# 2-Amplifier.net
KiCad netlist of a schematic drawn in Altium Designer
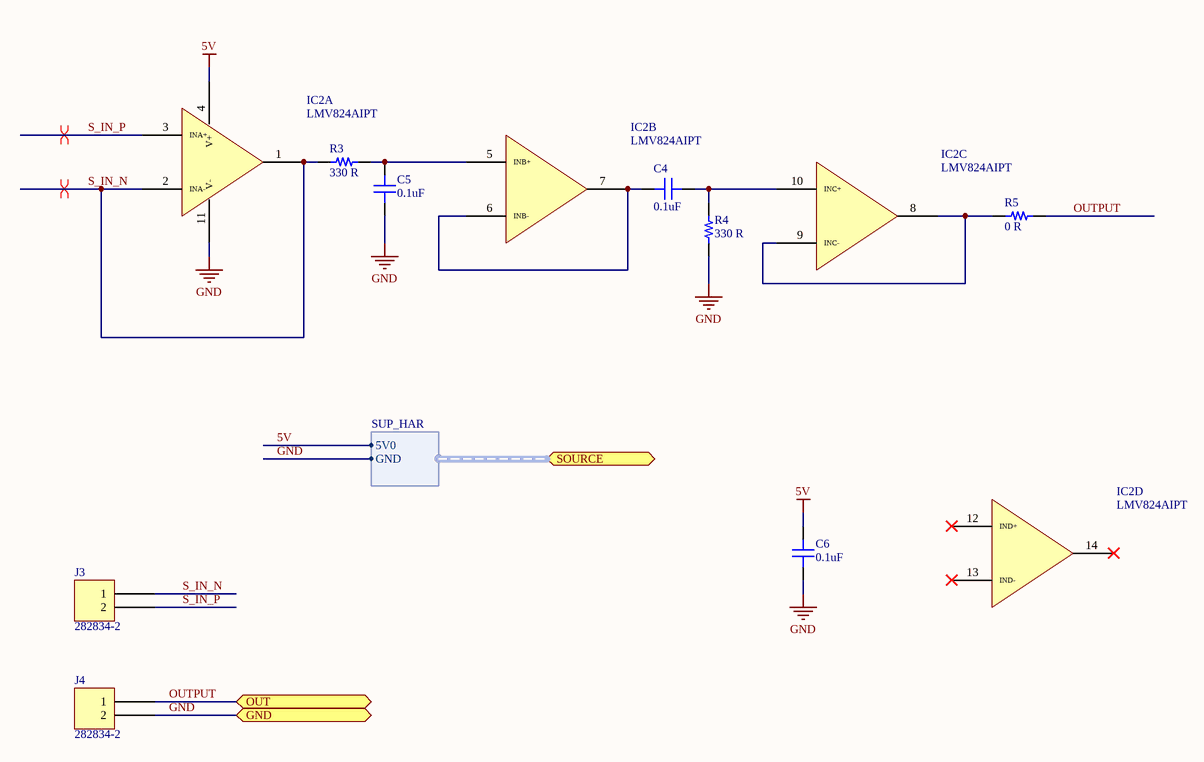
[diagram p0: 2-Amplifier.SchDoc]

(export (version "E")
  (design (tool "Eeschema 10.0.6"))
  (components
    (comp (ref "C4")
      (value "0.1uF")
      (footprint "CAP 0805_2012")
      (description "CAP CER 5.6PF 500V C0G/NP0 0805")
      (fields (field (name "PART NUMBER") "CBR08C569BCGAC") (field (name "MANUFACTURER") "KEMET"))
      (libsource (lib "Celestial Altium Library - altium_library") (part "Capacitor"))
    )
    (comp (ref "C5")
      (value "0.1uF")
      (footprint "CAP 0805_2012")
      (description "CAP CER 5.6PF 500V C0G/NP0 0805")
      (fields (field (name "PART NUMBER") "CBR08C569BCGAC") (field (name "MANUFACTURER") "KEMET"))
      (libsource (lib "Celestial Altium Library - altium_library") (part "Capacitor"))
    )
    (comp (ref "C6")
      (value "0.1uF")
      (footprint "CAP 0805_2012")
      (description "CAP CER 5.6PF 500V C0G/NP0 0805")
      (fields (field (name "PART NUMBER") "CBR08C569BCGAC") (field (name "MANUFACTURER") "KEMET"))
      (libsource (lib "Celestial Altium Library - altium_library") (part "Capacitor"))
    )
    (comp (ref "IC2")
      (value "LMV824AIPT")
      (footprint "TI TSSOP-14 PW")
      (description "IC OPAMP GP 4 CIRCUIT 14TSSOP")
      (fields (field (name "MANUFACTURER") "STMicroelectronics"))
      (libsource (lib "Celestial Altium Library - altium_library") (part "TI LMV82x 14 PIN"))
    )
    (comp (ref "J3")
      (value "282834-2")
      (footprint "TE 282834-2")
      (description "TERM BLK 2P SIDE ENT 2.54MM PCB")
      (fields (field (name "MANUFACTURER") "TE Connectivity AMP Connectors") (field (name "VOLTAGE") "150V"))
      (libsource (lib "Celestial Altium Library - altium_library") (part "2 Pin"))
    )
    (comp (ref "J4")
      (value "282834-2")
      (footprint "TE 282834-2")
      (description "TERM BLK 2P SIDE ENT 2.54MM PCB")
      (fields (field (name "MANUFACTURER") "TE Connectivity AMP Connectors") (field (name "VOLTAGE") "150V"))
      (libsource (lib "Celestial Altium Library - altium_library") (part "2 Pin"))
    )
    (comp (ref "R3")
      (value "330 R")
      (footprint "RES 0805_2012")
      (description "RES 82K OHM 0.5% 1/8W 0805")
      (fields
        (field (name "PART NUMBER") "RNCF0805DTE82K0")
        (field (name "MANUFACTURER") "Stackpole Electronics Inc")
      )
      (libsource (lib "Celestial Altium Library - altium_library") (part "Resistor"))
    )
    (comp (ref "R4")
      (value "330 R")
      (footprint "RES 0805_2012")
      (description "RES 82K OHM 0.5% 1/8W 0805")
      (fields
        (field (name "PART NUMBER") "RNCF0805DTE82K0")
        (field (name "MANUFACTURER") "Stackpole Electronics Inc")
      )
      (libsource (lib "Celestial Altium Library - altium_library") (part "Resistor"))
    )
    (comp (ref "R5")
      (value "0 R")
      (footprint "RES 0805_2012")
      (description "RES 82K OHM 0.5% 1/8W 0805")
      (fields
        (field (name "PART NUMBER") "RNCF0805DTE82K0")
        (field (name "MANUFACTURER") "Stackpole Electronics Inc")
      )
      (libsource (lib "Celestial Altium Library - altium_library") (part "Resistor"))
    )
  )
  (nets
    (net (code "2") (name "/OUTPUT") (class "Default")
      (node (ref "J4") (pin "1") (pinfunction "1_1") (pintype "passive"))
      (node (ref "R5") (pin "1") (pinfunction "1_1") (pintype "passive"))
    )
    (net (code "3") (name "/S_IN_N") (class "Default")
      (node (ref "IC2") (pin "1") (pinfunction "OUT_1") (pintype "passive"))
      (node (ref "IC2") (pin "2") (pinfunction "INA-_2") (pintype "passive"))
      (node (ref "J3") (pin "1") (pinfunction "1_1") (pintype "passive"))
      (node (ref "R3") (pin "1") (pinfunction "1_1") (pintype "passive"))
    )
    (net (code "4") (name "/S_IN_P") (class "Default")
      (node (ref "IC2") (pin "3") (pinfunction "INA+_3") (pintype "passive"))
      (node (ref "J3") (pin "2") (pinfunction "2_2") (pintype "passive"))
    )
    (net (code "6") (name "5V") (class "Default")
      (node (ref "C6") (pin "2") (pinfunction "2_2") (pintype "passive"))
      (node (ref "IC2") (pin "4") (pinfunction "V+_4") (pintype "power_in"))
    )
    (net (code "7") (name "GND") (class "Default")
      (node (ref "C5") (pin "1") (pinfunction "1_1") (pintype "passive"))
      (node (ref "C6") (pin "1") (pinfunction "1_1") (pintype "passive"))
      (node (ref "IC2") (pin "11") (pinfunction "V-_11") (pintype "power_in"))
      (node (ref "J4") (pin "2") (pinfunction "2_2") (pintype "passive"))
      (node (ref "R4") (pin "1") (pinfunction "1_1") (pintype "passive"))
    )
    (net (code "8") (name "Net-(IC2B-INB+)") (class "Default")
      (node (ref "C5") (pin "2") (pinfunction "2_2") (pintype "passive"))
      (node (ref "IC2") (pin "5") (pinfunction "INB+_5") (pintype "passive"))
      (node (ref "R3") (pin "2") (pinfunction "2_2") (pintype "passive"))
    )
    (net (code "9") (name "Net-(IC2B-INB-)") (class "Default")
      (node (ref "C4") (pin "2") (pinfunction "2_2") (pintype "passive"))
      (node (ref "IC2") (pin "6") (pinfunction "INB-_6") (pintype "passive"))
      (node (ref "IC2") (pin "7") (pinfunction "OUTB_7") (pintype "passive"))
    )
    (net (code "10") (name "Net-(IC2C-INC+)") (class "Default")
      (node (ref "C4") (pin "1") (pinfunction "1_1") (pintype "passive"))
      (node (ref "IC2") (pin "10") (pinfunction "INC+_10") (pintype "passive"))
      (node (ref "R4") (pin "2") (pinfunction "2_2") (pintype "passive"))
    )
    (net (code "11") (name "Net-(IC2C-INC-)") (class "Default")
      (node (ref "IC2") (pin "8") (pinfunction "OUTC_8") (pintype "passive"))
      (node (ref "IC2") (pin "9") (pinfunction "INC-_9") (pintype "passive"))
      (node (ref "R5") (pin "2") (pinfunction "2_2") (pintype "passive"))
    )
    (net (code "12") (name "unconnected-(IC2D-IND+-Pad12)") (class "Default")
      (node (ref "IC2") (pin "12") (pinfunction "IND+_12") (pintype "passive+no_connect"))
    )
    (net (code "13") (name "unconnected-(IC2D-IND--Pad13)") (class "Default")
      (node (ref "IC2") (pin "13") (pinfunction "IND-_13") (pintype "passive+no_connect"))
    )
    (net (code "14") (name "unconnected-(IC2D-OUTD-Pad14)") (class "Default")
      (node (ref "IC2") (pin "14") (pinfunction "OUTD_14") (pintype "passive+no_connect"))
    )
  )
)
